# TC364_MainBoard_Power_V1_1.net
KiCad netlist of a schematic drawn in Altium Designer
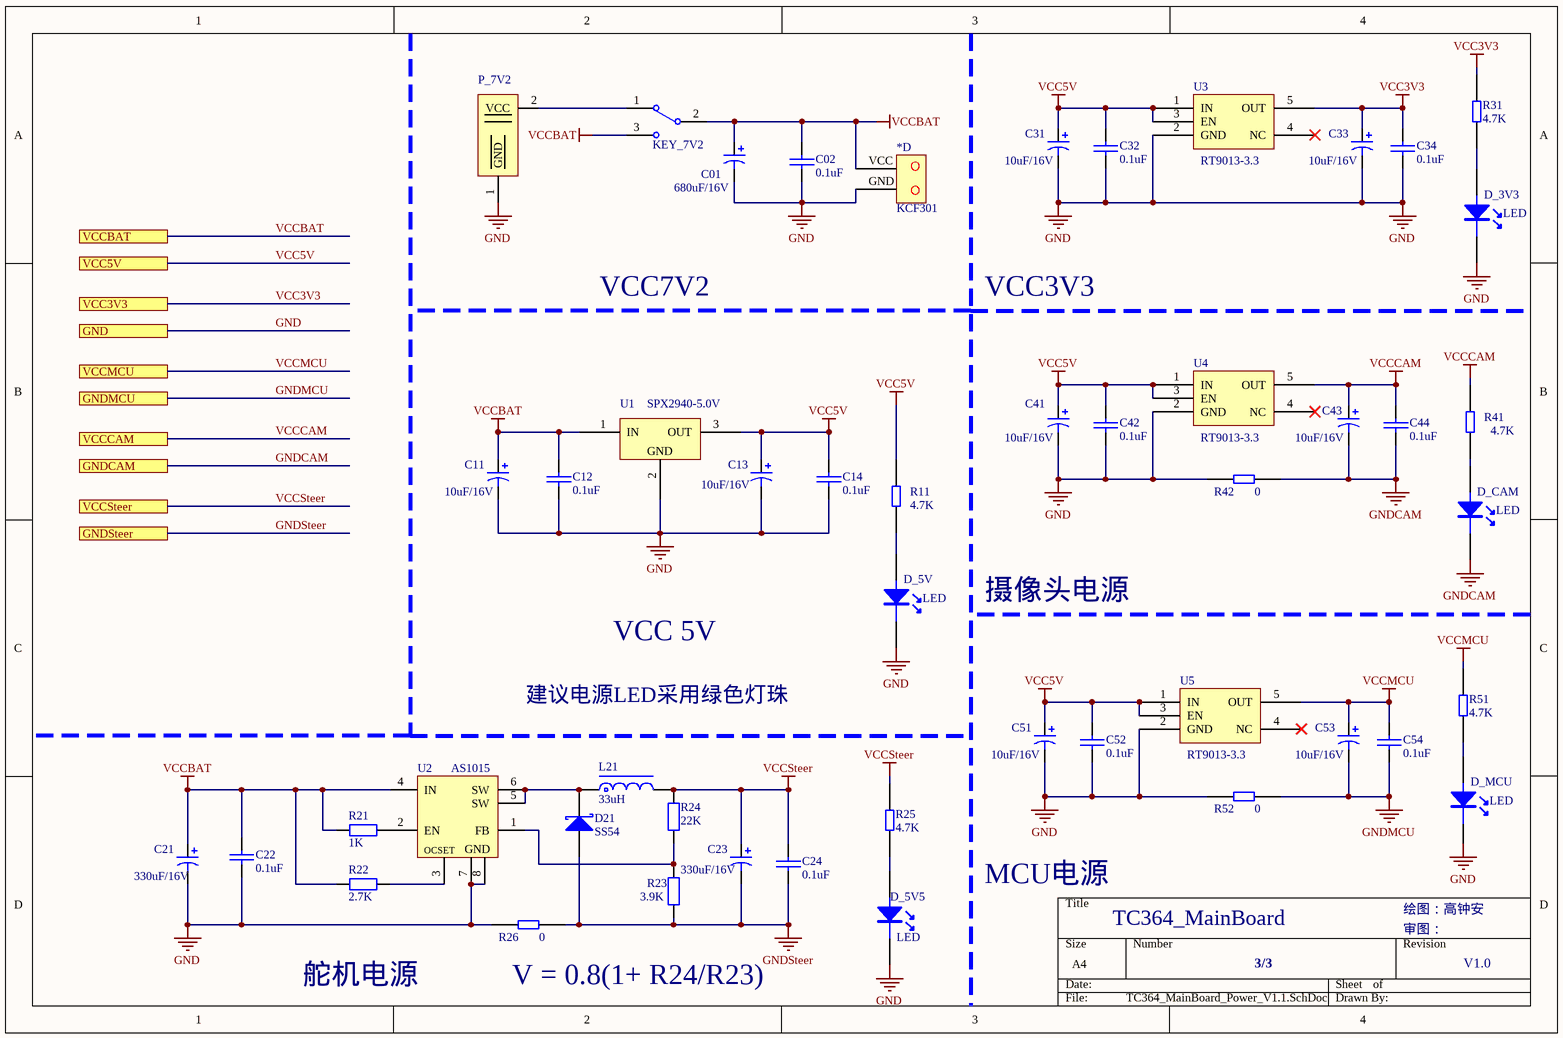
[diagram p0: TC364_MainBoard_Power_V1.1.SchDoc]

(export (version "E")
  (design (tool "Eeschema 10.0.6"))
  (components
    (comp (ref "*") (value "KCF301") (footprint "KF301-2P") (libsource (lib "BaseLib_SCH") (part "KCF301")))
    (comp (ref "C01")
      (value "680uF/16V")
      (footprint "CAP 3.5*8*11.5 - GD")
      (description "Polarized Capacitor (Radial)")
      (fields (field (name "PUBLISHER") "Altium Limited"))
      (libsource (lib "Miscellaneous Devices") (part "Cap Pol1"))
    )
    (comp (ref "C02")
      (value "0.1uF")
      (footprint "0805C")
      (description "Capacitor")
      (libsource (lib "Protel99Lib_SCH") (part "CAP"))
    )
    (comp (ref "C11")
      (value "10uF/16V")
      (footprint "CASE-A_3216")
      (description "Polarized Capacitor (Radial)")
      (fields (field (name "PUBLISHER") "Altium Limited"))
      (libsource (lib "Miscellaneous Devices") (part "Cap Pol1"))
    )
    (comp (ref "C12")
      (value "0.1uF")
      (footprint "0805C")
      (description "Capacitor")
      (libsource (lib "Protel99Lib_SCH") (part "CAP"))
    )
    (comp (ref "C13")
      (value "10uF/16V")
      (footprint "CASE-A_3216")
      (description "Polarized Capacitor (Radial)")
      (fields (field (name "PUBLISHER") "Altium Limited"))
      (libsource (lib "Miscellaneous Devices") (part "Cap Pol1"))
    )
    (comp (ref "C14")
      (value "0.1uF")
      (footprint "0805C")
      (description "Capacitor")
      (libsource (lib "Protel99Lib_SCH") (part "CAP"))
    )
    (comp (ref "C21")
      (value "330uF/16V")
      (footprint "CAP 2.5*6.3*11.2 - BK")
      (description "Polarized Capacitor (Radial)")
      (fields (field (name "PUBLISHER") "Altium Limited"))
      (libsource (lib "Miscellaneous Devices") (part "Cap Pol1"))
    )
    (comp (ref "C22")
      (value "0.1uF")
      (footprint "0805C")
      (description "Capacitor")
      (libsource (lib "Protel99Lib_SCH") (part "CAP"))
    )
    (comp (ref "C23")
      (value "330uF/16V")
      (footprint "CAP 2.5*6.3*11.2 - BK")
      (description "Polarized Capacitor (Radial)")
      (fields (field (name "PUBLISHER") "Altium Limited"))
      (libsource (lib "Miscellaneous Devices") (part "Cap Pol1"))
    )
    (comp (ref "C24")
      (value "0.1uF")
      (footprint "0805C")
      (description "Capacitor")
      (libsource (lib "Protel99Lib_SCH") (part "CAP"))
    )
    (comp (ref "C31")
      (value "10uF/16V")
      (footprint "CASE-A_3216")
      (description "Polarized Capacitor (Radial)")
      (fields (field (name "PUBLISHER") "Altium Limited"))
      (libsource (lib "Miscellaneous Devices") (part "Cap Pol1"))
    )
    (comp (ref "C32")
      (value "0.1uF")
      (footprint "0805C")
      (description "Capacitor")
      (libsource (lib "Protel99Lib_SCH") (part "CAP"))
    )
    (comp (ref "C33")
      (value "10uF/16V")
      (footprint "CASE-A_3216")
      (description "Polarized Capacitor (Radial)")
      (fields (field (name "PUBLISHER") "Altium Limited"))
      (libsource (lib "Miscellaneous Devices") (part "Cap Pol1"))
    )
    (comp (ref "C34")
      (value "0.1uF")
      (footprint "0805C")
      (description "Capacitor")
      (libsource (lib "Protel99Lib_SCH") (part "CAP"))
    )
    (comp (ref "C41")
      (value "10uF/16V")
      (footprint "CASE-A_3216")
      (description "Polarized Capacitor (Radial)")
      (fields (field (name "PUBLISHER") "Altium Limited"))
      (libsource (lib "Miscellaneous Devices") (part "Cap Pol1"))
    )
    (comp (ref "C42")
      (value "0.1uF")
      (footprint "0805C")
      (description "Capacitor")
      (libsource (lib "Protel99Lib_SCH") (part "CAP"))
    )
    (comp (ref "C43")
      (value "10uF/16V")
      (footprint "CASE-A_3216")
      (description "Polarized Capacitor (Radial)")
      (fields (field (name "PUBLISHER") "Altium Limited"))
      (libsource (lib "Miscellaneous Devices") (part "Cap Pol1"))
    )
    (comp (ref "C44")
      (value "0.1uF")
      (footprint "0805C")
      (description "Capacitor")
      (libsource (lib "Protel99Lib_SCH") (part "CAP"))
    )
    (comp (ref "C51")
      (value "10uF/16V")
      (footprint "CASE-A_3216")
      (description "Polarized Capacitor (Radial)")
      (fields (field (name "PUBLISHER") "Altium Limited"))
      (libsource (lib "Miscellaneous Devices") (part "Cap Pol1"))
    )
    (comp (ref "C52")
      (value "0.1uF")
      (footprint "0805C")
      (description "Capacitor")
      (libsource (lib "Protel99Lib_SCH") (part "CAP"))
    )
    (comp (ref "C53")
      (value "10uF/16V")
      (footprint "CASE-A_3216")
      (description "Polarized Capacitor (Radial)")
      (fields (field (name "PUBLISHER") "Altium Limited"))
      (libsource (lib "Miscellaneous Devices") (part "Cap Pol1"))
    )
    (comp (ref "C54")
      (value "0.1uF")
      (footprint "0805C")
      (description "Capacitor")
      (libsource (lib "Protel99Lib_SCH") (part "CAP"))
    )
    (comp (ref "D21")
      (value "SS54")
      (footprint "SMA")
      (description "肖特基二极管")
      (libsource (lib "0.2 -  二极管-整流桥") (part "SS34"))
    )
    (comp (ref "D_3V3")
      (value "LED")
      (footprint "0805_LED_S1")
      (description "发光二极管")
      (libsource (lib "jianing") (part "LED"))
    )
    (comp (ref "D_5V")
      (value "LED")
      (footprint "0805_LED_S1")
      (description "发光二极管")
      (libsource (lib "jianing") (part "LED"))
    )
    (comp (ref "D_5V5")
      (value "LED")
      (footprint "0805_LED_S1")
      (description "发光二极管")
      (libsource (lib "jianing") (part "LED"))
    )
    (comp (ref "D_CAM")
      (value "LED")
      (footprint "0805_LED_S1")
      (description "发光二极管")
      (libsource (lib "jianing") (part "LED"))
    )
    (comp (ref "D_MCU")
      (value "LED")
      (footprint "0805_LED_S1")
      (description "发光二极管")
      (libsource (lib "jianing") (part "LED"))
    )
    (comp (ref "KEY_7V2")
      (value "SS-12F23")
      (footprint "KEY_7V2")
      (description "1路波动开关")
      (fields (field (name "版权归属") "封装库来自淘宝 ID：黄晶宝石"))
      (libsource (lib "0.7 - 常用按键-开关") (part "SSW-1P"))
    )
    (comp (ref "L21")
      (value "33uH")
      (footprint "7*7 L")
      (description "功率屏蔽电感")
      (fields (field (name "版权归属") "封装库来自淘宝 ID：黄晶宝石"))
      (libsource (lib "0.1 - 电阻-电容-电感") (part "L-CDRH"))
    )
    (comp (ref "P_7V2")
      (value "T_Type_Adapter")
      (footprint "T_Type_Adapter")
      (libsource (lib "Schlib1") (part "T_Type_Adapter"))
    )
    (comp (ref "R11") (value "4.7K") (footprint "0805R") (libsource (lib "BaseLib_SCH") (part "RES")))
    (comp (ref "R21")
      (value "1K")
      (footprint "0805R")
      (description "贴片电阻")
      (fields (field (name "版权归属") "源创客"))
      (libsource (lib "jianing") (part "RES"))
    )
    (comp (ref "R22")
      (value "2.7K")
      (footprint "0805R")
      (description "贴片电阻")
      (fields (field (name "版权归属") "源创客"))
      (libsource (lib "jianing") (part "RES"))
    )
    (comp (ref "R23")
      (value "3.9K")
      (footprint "0805R")
      (description "贴片电阻")
      (fields (field (name "版权归属") "源创客"))
      (libsource (lib "jianing") (part "RES"))
    )
    (comp (ref "R24")
      (value "22K")
      (footprint "0805R")
      (description "贴片电阻")
      (fields (field (name "版权归属") "源创客"))
      (libsource (lib "jianing") (part "RES"))
    )
    (comp (ref "R25") (value "4.7K") (footprint "0805R") (libsource (lib "BaseLib_SCH") (part "RES")))
    (comp (ref "R26") (value "0") (footprint "0805R") (libsource (lib "BaseLib_SCH") (part "RES")))
    (comp (ref "R31") (value "4.7K") (footprint "0805R") (libsource (lib "BaseLib_SCH") (part "RES")))
    (comp (ref "R41") (value "4.7K") (footprint "0805R") (libsource (lib "BaseLib_SCH") (part "RES")))
    (comp (ref "R42") (value "0") (footprint "0805R") (libsource (lib "BaseLib_SCH") (part "RES")))
    (comp (ref "R51") (value "4.7K") (footprint "0805R") (libsource (lib "BaseLib_SCH") (part "RES")))
    (comp (ref "R52") (value "0") (footprint "0805R") (libsource (lib "BaseLib_SCH") (part "RES")))
    (comp (ref "U1")
      (value "SPX2940-5.0V")
      (footprint "TO-220(TO-220-3)")
      (description "5V稳压芯片")
      (fields (field (name "版权归属") "封装库来自淘宝 ID：黄晶宝石"))
      (libsource (lib "1.1 - 电源类芯片") (part "LM2940"))
    )
    (comp (ref "U2")
      (value "AS1015")
      (footprint "SOP-8_150mil")
      (description "可调升压芯片")
      (libsource (lib "1.0 - 常见芯片") (part "AS1015"))
    )
    (comp (ref "U3")
      (value "RT9013-3.3")
      (footprint "SOT-23-5")
      (libsource (lib "jianing") (part "RT9013-3.3"))
    )
    (comp (ref "U4")
      (value "RT9013-3.3")
      (footprint "SOT-23-5")
      (libsource (lib "jianing") (part "RT9013-3.3"))
    )
    (comp (ref "U5")
      (value "RT9013-3.3")
      (footprint "SOT-23-5")
      (libsource (lib "jianing") (part "RT9013-3.3"))
    )
  )
  (nets
    (net (code "1") (name "GND") (class "Default")
      (node (ref "C01") (pin "2") (pinfunction "2_2") (pintype "passive"))
      (node (ref "C02") (pin "2") (pinfunction "2_2") (pintype "passive"))
      (node (ref "C11") (pin "2") (pinfunction "2_2") (pintype "passive"))
      (node (ref "C12") (pin "2") (pinfunction "2_2") (pintype "passive"))
      (node (ref "C13") (pin "2") (pinfunction "2_2") (pintype "passive"))
      (node (ref "C14") (pin "2") (pinfunction "2_2") (pintype "passive"))
      (node (ref "C21") (pin "2") (pinfunction "2_2") (pintype "passive"))
      (node (ref "C22") (pin "2") (pinfunction "2_2") (pintype "passive"))
      (node (ref "C31") (pin "2") (pinfunction "2_2") (pintype "passive"))
      (node (ref "C32") (pin "2") (pinfunction "2_2") (pintype "passive"))
      (node (ref "C33") (pin "2") (pinfunction "2_2") (pintype "passive"))
      (node (ref "C34") (pin "2") (pinfunction "2_2") (pintype "passive"))
      (node (ref "C41") (pin "2") (pinfunction "2_2") (pintype "passive"))
      (node (ref "C42") (pin "2") (pinfunction "2_2") (pintype "passive"))
      (node (ref "C51") (pin "2") (pinfunction "2_2") (pintype "passive"))
      (node (ref "C52") (pin "2") (pinfunction "2_2") (pintype "passive"))
      (node (ref "D_3V3") (pin "K") (pinfunction "2_K") (pintype "passive"))
      (node (ref "D_5V") (pin "K") (pinfunction "2_K") (pintype "passive"))
      (node (ref "D_5V5") (pin "K") (pinfunction "2_K") (pintype "passive"))
      (node (ref "P_7V2") (pin "1") (pinfunction "GND_1") (pintype "passive"))
      (node (ref "R26") (pin "2") (pinfunction "2_2") (pintype "passive"))
      (node (ref "R42") (pin "2") (pinfunction "2_2") (pintype "passive"))
      (node (ref "R52") (pin "2") (pinfunction "2_2") (pintype "passive"))
      (node (ref "U1") (pin "2") (pinfunction "GND_2") (pintype "power_in"))
      (node (ref "U2") (pin "7") (pinfunction "GND_7") (pintype "power_in"))
      (node (ref "U2") (pin "8") (pinfunction "GND_8") (pintype "power_in"))
      (node (ref "U3") (pin "2") (pinfunction "GND_2") (pintype "passive"))
      (node (ref "U4") (pin "2") (pinfunction "GND_2") (pintype "passive"))
      (node (ref "U5") (pin "2") (pinfunction "GND_2") (pintype "passive"))
    )
    (net (code "2") (name "GNDCAM") (class "Default")
      (node (ref "C43") (pin "2") (pinfunction "2_2") (pintype "passive"))
      (node (ref "C44") (pin "2") (pinfunction "2_2") (pintype "passive"))
      (node (ref "D_CAM") (pin "K") (pinfunction "2_K") (pintype "passive"))
      (node (ref "R42") (pin "1") (pinfunction "1_1") (pintype "passive"))
    )
    (net (code "3") (name "GNDMCU") (class "Default")
      (node (ref "C53") (pin "2") (pinfunction "2_2") (pintype "passive"))
      (node (ref "C54") (pin "2") (pinfunction "2_2") (pintype "passive"))
      (node (ref "R52") (pin "1") (pinfunction "1_1") (pintype "passive"))
    )
    (net (code "4") (name "GNDSteer") (class "Default")
      (node (ref "C23") (pin "2") (pinfunction "2_2") (pintype "passive"))
      (node (ref "C24") (pin "2") (pinfunction "2_2") (pintype "passive"))
      (node (ref "D21") (pin "1") (pinfunction "A_1") (pintype "passive"))
      (node (ref "R23") (pin "2") (pinfunction "2_2") (pintype "passive"))
      (node (ref "R26") (pin "1") (pinfunction "1_1") (pintype "passive"))
    )
    (net (code "5") (name "Net-(D21-K)") (class "Default")
      (node (ref "D21") (pin "2") (pinfunction "K_2") (pintype "passive"))
      (node (ref "L21") (pin "1") (pinfunction "1_1") (pintype "passive"))
      (node (ref "U2") (pin "5") (pinfunction "SW_5") (pintype "power_in"))
      (node (ref "U2") (pin "6") (pinfunction "SW_6") (pintype "power_in"))
    )
    (net (code "6") (name "Net-(D_3V3-1)") (class "Default")
      (node (ref "D_3V3") (pin "A") (pinfunction "1_A") (pintype "passive"))
      (node (ref "R31") (pin "2") (pinfunction "2_2") (pintype "passive"))
    )
    (net (code "7") (name "Net-(D_5V-1)") (class "Default")
      (node (ref "D_5V") (pin "A") (pinfunction "1_A") (pintype "passive"))
      (node (ref "R11") (pin "2") (pinfunction "2_2") (pintype "passive"))
    )
    (net (code "8") (name "Net-(D_5V5-1)") (class "Default")
      (node (ref "D_5V5") (pin "A") (pinfunction "1_A") (pintype "passive"))
      (node (ref "R25") (pin "2") (pinfunction "2_2") (pintype "passive"))
    )
    (net (code "9") (name "Net-(D_CAM-1)") (class "Default")
      (node (ref "D_CAM") (pin "A") (pinfunction "1_A") (pintype "passive"))
      (node (ref "R41") (pin "2") (pinfunction "2_2") (pintype "passive"))
    )
    (net (code "10") (name "Net-(D_MCU-1)") (class "Default")
      (node (ref "D_MCU") (pin "A") (pinfunction "1_A") (pintype "passive"))
      (node (ref "R51") (pin "2") (pinfunction "2_2") (pintype "passive"))
    )
    (net (code "11") (name "Net-(P_7V2-VCC)") (class "Default")
      (node (ref "KEY_7V2") (pin "1") (pinfunction "1_1") (pintype "passive"))
      (node (ref "P_7V2") (pin "2") (pinfunction "VCC_2") (pintype "passive"))
    )
    (net (code "12") (name "Net-(U2-EN)") (class "Default")
      (node (ref "R21") (pin "1") (pinfunction "1_1") (pintype "passive"))
      (node (ref "U2") (pin "2") (pinfunction "EN_2") (pintype "power_in"))
    )
    (net (code "13") (name "Net-(U2-FB)") (class "Default")
      (node (ref "R23") (pin "1") (pinfunction "1_1") (pintype "passive"))
      (node (ref "R24") (pin "2") (pinfunction "2_2") (pintype "passive"))
      (node (ref "U2") (pin "1") (pinfunction "FB_1") (pintype "power_in"))
    )
    (net (code "14") (name "Net-(U2-OCSET)") (class "Default")
      (node (ref "R22") (pin "1") (pinfunction "1_1") (pintype "passive"))
      (node (ref "U2") (pin "3") (pinfunction "OCSET_3") (pintype "power_in"))
    )
    (net (code "15") (name "VCC3V3") (class "Default")
      (node (ref "C33") (pin "1") (pinfunction "1_1") (pintype "passive"))
      (node (ref "C34") (pin "1") (pinfunction "1_1") (pintype "passive"))
      (node (ref "R31") (pin "1") (pinfunction "1_1") (pintype "passive"))
      (node (ref "U3") (pin "5") (pinfunction "OUT_5") (pintype "passive"))
    )
    (net (code "16") (name "VCC5V") (class "Default")
      (node (ref "C13") (pin "1") (pinfunction "1_1") (pintype "passive"))
      (node (ref "C14") (pin "1") (pinfunction "1_1") (pintype "passive"))
      (node (ref "C31") (pin "1") (pinfunction "1_1") (pintype "passive"))
      (node (ref "C32") (pin "1") (pinfunction "1_1") (pintype "passive"))
      (node (ref "C41") (pin "1") (pinfunction "1_1") (pintype "passive"))
      (node (ref "C42") (pin "1") (pinfunction "1_1") (pintype "passive"))
      (node (ref "C51") (pin "1") (pinfunction "1_1") (pintype "passive"))
      (node (ref "C52") (pin "1") (pinfunction "1_1") (pintype "passive"))
      (node (ref "R11") (pin "1") (pinfunction "1_1") (pintype "passive"))
      (node (ref "U1") (pin "3") (pinfunction "OUT_3") (pintype "power_in"))
      (node (ref "U3") (pin "1") (pinfunction "IN_1") (pintype "passive"))
      (node (ref "U3") (pin "3") (pinfunction "EN_3") (pintype "passive"))
      (node (ref "U4") (pin "1") (pinfunction "IN_1") (pintype "passive"))
      (node (ref "U4") (pin "3") (pinfunction "EN_3") (pintype "passive"))
      (node (ref "U5") (pin "1") (pinfunction "IN_1") (pintype "passive"))
      (node (ref "U5") (pin "3") (pinfunction "EN_3") (pintype "passive"))
    )
    (net (code "17") (name "VCCBAT") (class "Default")
      (node (ref "C01") (pin "1") (pinfunction "1_1") (pintype "passive"))
      (node (ref "C02") (pin "1") (pinfunction "1_1") (pintype "passive"))
      (node (ref "C11") (pin "1") (pinfunction "1_1") (pintype "passive"))
      (node (ref "C12") (pin "1") (pinfunction "1_1") (pintype "passive"))
      (node (ref "C21") (pin "1") (pinfunction "1_1") (pintype "passive"))
      (node (ref "C22") (pin "1") (pinfunction "1_1") (pintype "passive"))
      (node (ref "KEY_7V2") (pin "2") (pinfunction "2_2") (pintype "passive"))
      (node (ref "KEY_7V2") (pin "3") (pinfunction "3_3") (pintype "passive"))
      (node (ref "R21") (pin "2") (pinfunction "2_2") (pintype "passive"))
      (node (ref "R22") (pin "2") (pinfunction "2_2") (pintype "passive"))
      (node (ref "U1") (pin "1") (pinfunction "IN_1") (pintype "power_in"))
      (node (ref "U2") (pin "4") (pinfunction "IN_4") (pintype "power_in"))
    )
    (net (code "18") (name "VCCCAM") (class "Default")
      (node (ref "C43") (pin "1") (pinfunction "1_1") (pintype "passive"))
      (node (ref "C44") (pin "1") (pinfunction "1_1") (pintype "passive"))
      (node (ref "R41") (pin "1") (pinfunction "1_1") (pintype "passive"))
      (node (ref "U4") (pin "5") (pinfunction "OUT_5") (pintype "passive"))
    )
    (net (code "19") (name "VCCMCU") (class "Default")
      (node (ref "C53") (pin "1") (pinfunction "1_1") (pintype "passive"))
      (node (ref "C54") (pin "1") (pinfunction "1_1") (pintype "passive"))
      (node (ref "R51") (pin "1") (pinfunction "1_1") (pintype "passive"))
      (node (ref "U5") (pin "5") (pinfunction "OUT_5") (pintype "passive"))
    )
    (net (code "20") (name "VCCSteer") (class "Default")
      (node (ref "C23") (pin "1") (pinfunction "1_1") (pintype "passive"))
      (node (ref "C24") (pin "1") (pinfunction "1_1") (pintype "passive"))
      (node (ref "L21") (pin "2") (pinfunction "2_2") (pintype "passive"))
      (node (ref "R24") (pin "1") (pinfunction "1_1") (pintype "passive"))
      (node (ref "R25") (pin "1") (pinfunction "1_1") (pintype "passive"))
    )
    (net (code "21") (name "unconnected-(*D-0-PadVCC)") (class "Default")
      (node (ref "*") (pin "VCC") (pinfunction "0_VCC") (pintype "passive"))
    )
    (net (code "22") (name "unconnected-(*D-1-PadGND)") (class "Default")
      (node (ref "*") (pin "GND") (pinfunction "1_GND") (pintype "passive"))
    )
    (net (code "23") (name "unconnected-(D_MCU-2-PadK)") (class "Default")
      (node (ref "D_MCU") (pin "K") (pinfunction "2_K") (pintype "passive"))
    )
    (net (code "24") (name "unconnected-(U3-NC-Pad4)") (class "Default")
      (node (ref "U3") (pin "4") (pinfunction "NC_4") (pintype "passive+no_connect"))
    )
    (net (code "25") (name "unconnected-(U4-NC-Pad4)") (class "Default")
      (node (ref "U4") (pin "4") (pinfunction "NC_4") (pintype "passive+no_connect"))
    )
    (net (code "26") (name "unconnected-(U5-NC-Pad4)") (class "Default")
      (node (ref "U5") (pin "4") (pinfunction "NC_4") (pintype "passive+no_connect"))
    )
  )
)
